# board.net
KiCad netlist of a schematic drawn in EAGLE
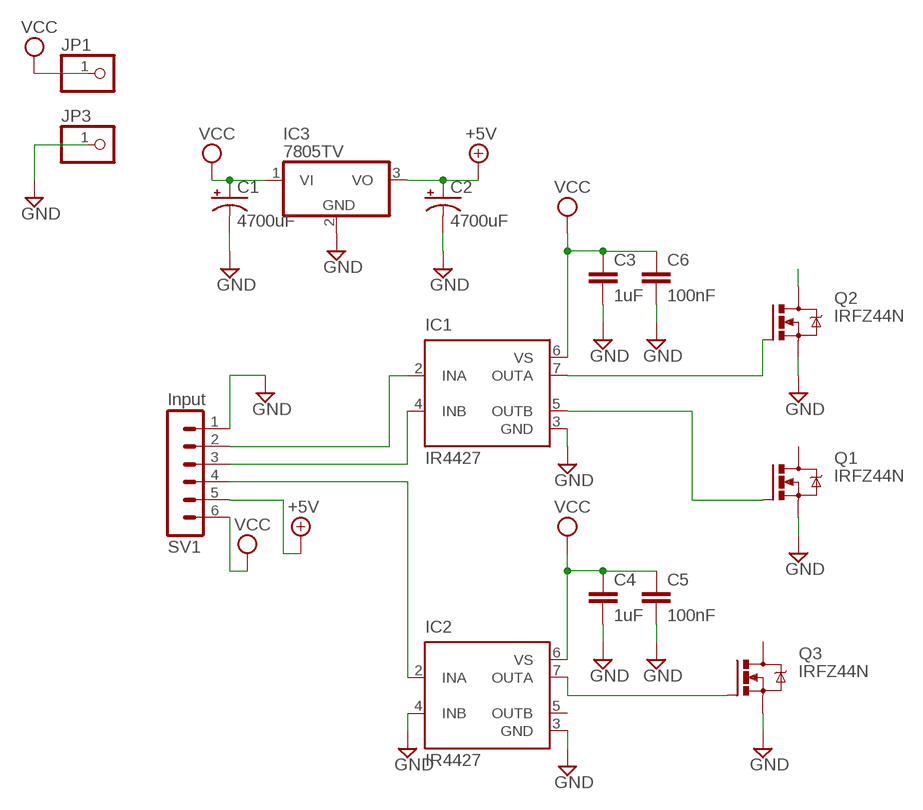
[diagram p0: schematic, sheet 1]

(export (version "E")
  (design (tool "Eeschema 10.0.6"))
  (components
    (comp (ref "C1")
      (value "4700uF")
      (footprint "eagle-import:E7,5-18")
      (libsource (lib "eagle-import") (part "CPOL-USE7.5-18"))
    )
    (comp (ref "C2")
      (value "4700uF")
      (footprint "eagle-import:E7,5-18")
      (libsource (lib "eagle-import") (part "CPOL-USE7.5-18"))
    )
    (comp (ref "C3")
      (value "1uF")
      (footprint "eagle-import:C050-050X075")
      (libsource (lib "eagle-import") (part "C-EU050-050X075"))
    )
    (comp (ref "C4")
      (value "1uF")
      (footprint "eagle-import:C050-050X075")
      (libsource (lib "eagle-import") (part "C-EU050-050X075"))
    )
    (comp (ref "C5")
      (value "100nF")
      (footprint "eagle-import:C050-024X044")
      (libsource (lib "eagle-import") (part "C-EU050-024X044"))
    )
    (comp (ref "C6")
      (value "100nF")
      (footprint "eagle-import:C050-024X044")
      (libsource (lib "eagle-import") (part "C-EU050-024X044"))
    )
    (comp (ref "IC1")
      (value "IR4427")
      (footprint "eagle-import:DIL08")
      (fields (field (name "MF") "INTERNATIONAL RECTIFIER(IR)"))
      (libsource (lib "eagle-import") (part "IR4427"))
    )
    (comp (ref "IC2")
      (value "IR4427")
      (footprint "eagle-import:DIL08")
      (fields (field (name "MF") "INTERNATIONAL RECTIFIER(IR)"))
      (libsource (lib "eagle-import") (part "IR4427"))
    )
    (comp (ref "IC3")
      (value "7805TV")
      (footprint "eagle-import:TO220V")
      (libsource (lib "eagle-import") (part "78TV05"))
    )
    (comp (ref "JP1")
      (value "PINHD-1X1")
      (footprint "eagle-import:1X01")
      (libsource (lib "eagle-import") (part "PINHD-1X1"))
    )
    (comp (ref "JP3")
      (value "PINHD-1X1")
      (footprint "eagle-import:1X01")
      (libsource (lib "eagle-import") (part "PINHD-1X1"))
    )
    (comp (ref "Q1")
      (value "IRFZ44N")
      (footprint "eagle-import:TO220BV")
      (libsource (lib "eagle-import") (part "IRF540"))
    )
    (comp (ref "Q2")
      (value "IRFZ44N")
      (footprint "eagle-import:TO220BV")
      (libsource (lib "eagle-import") (part "IRF540"))
    )
    (comp (ref "Q3")
      (value "IRFZ44N")
      (footprint "eagle-import:TO220BV")
      (libsource (lib "eagle-import") (part "IRF540"))
    )
    (comp (ref "SV1")
      (value "Input")
      (footprint "eagle-import:MA06-1")
      (libsource (lib "eagle-import") (part "MA06-1"))
    )
  )
  (nets
    (net (code "1") (name "+5V") (class "Default")
      (node (ref "C2") (pin "+") (pinfunction "+_+") (pintype "passive"))
      (node (ref "IC3") (pin "3") (pinfunction "VO_3") (pintype "passive"))
      (node (ref "SV1") (pin "5") (pinfunction "5_5") (pintype "passive"))
    )
    (net (code "2") (name "GND") (class "Default")
      (node (ref "C1") (pin "-") (pinfunction "-_-") (pintype "passive"))
      (node (ref "C2") (pin "-") (pinfunction "-_-") (pintype "passive"))
      (node (ref "C3") (pin "2") (pinfunction "2_2") (pintype "passive"))
      (node (ref "C4") (pin "2") (pinfunction "2_2") (pintype "passive"))
      (node (ref "C5") (pin "2") (pinfunction "2_2") (pintype "passive"))
      (node (ref "C6") (pin "2") (pinfunction "2_2") (pintype "passive"))
      (node (ref "IC1") (pin "3") (pinfunction "GND_3") (pintype "power_in"))
      (node (ref "IC2") (pin "3") (pinfunction "GND_3") (pintype "power_in"))
      (node (ref "IC2") (pin "4") (pinfunction "INB_4") (pintype "input"))
      (node (ref "IC3") (pin "2") (pinfunction "GND_2") (pintype "passive"))
      (node (ref "JP3") (pin "1") (pinfunction "1_1") (pintype "passive"))
      (node (ref "Q1") (pin "S") (pinfunction "S_S") (pintype "passive"))
      (node (ref "Q2") (pin "S") (pinfunction "S_S") (pintype "passive"))
      (node (ref "Q3") (pin "S") (pinfunction "S_S") (pintype "passive"))
      (node (ref "SV1") (pin "1") (pinfunction "1_1") (pintype "passive"))
    )
    (net (code "3") (name "Net-(IC1-INA)") (class "Default")
      (node (ref "IC1") (pin "2") (pinfunction "INA_2") (pintype "input"))
      (node (ref "SV1") (pin "2") (pinfunction "2_2") (pintype "passive"))
    )
    (net (code "4") (name "Net-(IC1-INB)") (class "Default")
      (node (ref "IC1") (pin "4") (pinfunction "INB_4") (pintype "input"))
      (node (ref "SV1") (pin "3") (pinfunction "3_3") (pintype "passive"))
    )
    (net (code "5") (name "Net-(IC1-OUTA)") (class "Default")
      (node (ref "IC1") (pin "7") (pinfunction "OUTA_7") (pintype "output"))
      (node (ref "Q2") (pin "G") (pinfunction "G_G") (pintype "passive"))
    )
    (net (code "6") (name "Net-(IC1-OUTB)") (class "Default")
      (node (ref "IC1") (pin "5") (pinfunction "OUTB_5") (pintype "output"))
      (node (ref "Q1") (pin "G") (pinfunction "G_G") (pintype "passive"))
    )
    (net (code "7") (name "Net-(IC2-INA)") (class "Default")
      (node (ref "IC2") (pin "2") (pinfunction "INA_2") (pintype "input"))
      (node (ref "SV1") (pin "4") (pinfunction "4_4") (pintype "passive"))
    )
    (net (code "8") (name "Net-(IC2-OUTA)") (class "Default")
      (node (ref "IC2") (pin "7") (pinfunction "OUTA_7") (pintype "output"))
      (node (ref "Q3") (pin "G") (pinfunction "G_G") (pintype "passive"))
    )
    (net (code "9") (name "VCC") (class "Default")
      (node (ref "C1") (pin "+") (pinfunction "+_+") (pintype "passive"))
      (node (ref "C3") (pin "1") (pinfunction "1_1") (pintype "passive"))
      (node (ref "C4") (pin "1") (pinfunction "1_1") (pintype "passive"))
      (node (ref "C5") (pin "1") (pinfunction "1_1") (pintype "passive"))
      (node (ref "C6") (pin "1") (pinfunction "1_1") (pintype "passive"))
      (node (ref "IC1") (pin "6") (pinfunction "VS_6") (pintype "power_in"))
      (node (ref "IC2") (pin "6") (pinfunction "VS_6") (pintype "power_in"))
      (node (ref "IC3") (pin "1") (pinfunction "VI_1") (pintype "input"))
      (node (ref "JP1") (pin "1") (pinfunction "1_1") (pintype "passive"))
      (node (ref "SV1") (pin "6") (pinfunction "6_6") (pintype "passive"))
    )
    (net (code "10") (name "unconnected-(IC2-OUTB-Pad5)") (class "Default")
      (node (ref "IC2") (pin "5") (pinfunction "OUTB_5") (pintype "output"))
    )
    (net (code "11") (name "unconnected-(Q1-PadD)") (class "Default")
      (node (ref "Q1") (pin "D") (pinfunction "D_D") (pintype "passive"))
    )
    (net (code "12") (name "unconnected-(Q2-PadD)") (class "Default")
      (node (ref "Q2") (pin "D") (pinfunction "D_D") (pintype "passive"))
    )
    (net (code "13") (name "unconnected-(Q3-PadD)") (class "Default")
      (node (ref "Q3") (pin "D") (pinfunction "D_D") (pintype "passive"))
    )
  )
)
